# ContadorSincronico_SCH.net
KiCad netlist of a schematic drawn in Altium Designer
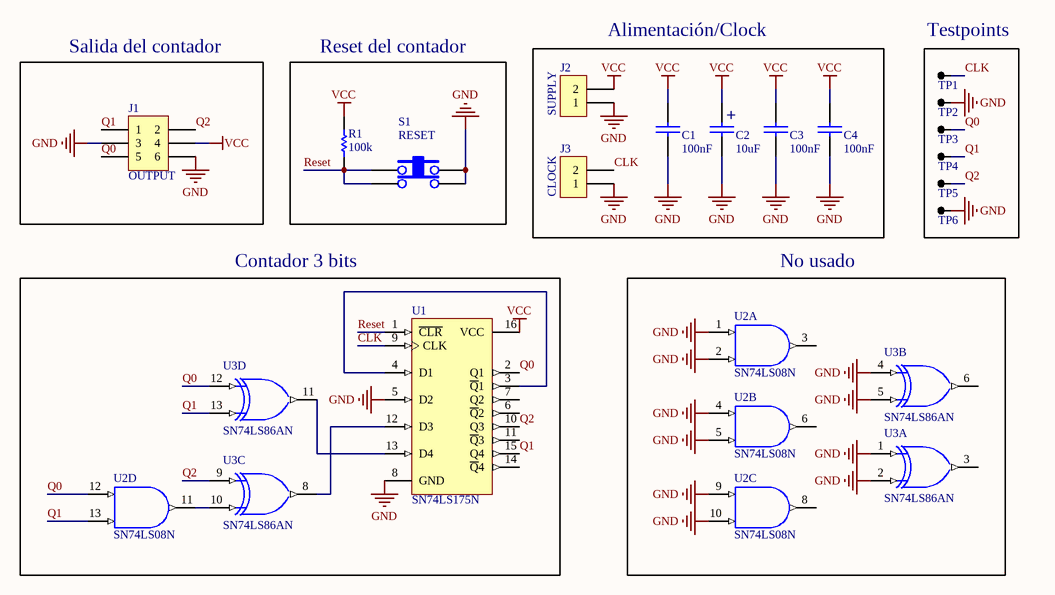
[diagram p0: ContadorSincronico_SCH.SchDoc]

(export (version "E")
  (design (tool "Eeschema 10.0.6"))
  (components
    (comp (ref "C1") (value "100nF") (footprint "0805") (libsource (lib "LIBEBAL") (part "CAP")))
    (comp (ref "C2") (value "10uF") (footprint "CAP100RP") (libsource (lib "LIBEBAL") (part "CAPPOL")))
    (comp (ref "C3") (value "100nF") (footprint "0805") (libsource (lib "LIBEBAL") (part "CAP")))
    (comp (ref "C4") (value "100nF") (footprint "0805") (libsource (lib "LIBEBAL") (part "CAP")))
    (comp (ref "J1") (value "OUTPUT") (footprint "SIP3*2") (libsource (lib "LIBEBAL") (part "CON3*2")))
    (comp (ref "J2") (value "SUPPLY") (footprint "BORNERA2") (libsource (lib "LIBEBAL") (part "BORNERA 2")))
    (comp (ref "J3") (value "CLOCK") (footprint "BORNERA2") (libsource (lib "LIBEBAL") (part "BORNERA 2")))
    (comp (ref "R1") (value "100k") (footprint "0805") (libsource (lib "LIBEBAL") (part "RES")))
    (comp (ref "S1")
      (value "RESET")
      (footprint "TACTSWITCH")
      (libsource (lib "LIBEBAL") (part "TACT SWITCH"))
    )
    (comp (ref "TP1") (value "CLK") (footprint "TPTH") (libsource (lib "LIBEBAL") (part "TP")))
    (comp (ref "TP2") (value "GND") (footprint "TPTH") (libsource (lib "LIBEBAL") (part "TP")))
    (comp (ref "TP3") (value "Q0") (footprint "TPTH") (libsource (lib "LIBEBAL") (part "TP")))
    (comp (ref "TP4") (value "Q1") (footprint "TPTH") (libsource (lib "LIBEBAL") (part "TP")))
    (comp (ref "TP5") (value "Q2") (footprint "TPTH") (libsource (lib "LIBEBAL") (part "TP")))
    (comp (ref "TP6") (value "GND") (footprint "TPTH") (libsource (lib "LIBEBAL") (part "TP")))
    (comp (ref "U1")
      (value "SN74LS175N")
      (footprint "N016")
      (description "Quadruple D-Type Flip-Flop with Clear")
      (fields (field (name "PUBLISHER") "Altium Limited"))
      (libsource (lib "TI Logic Flip-Flop") (part "SN74LS175N"))
    )
    (comp (ref "U2")
      (value "SN74LS08N")
      (footprint "N014")
      (description "Quadruple 2-Input Positive-AND Gate")
      (fields (field (name "PUBLISHER") "Altium Limited"))
      (libsource (lib "TI Logic Gate 2") (part "SN74LS08N"))
    )
    (comp (ref "U3")
      (value "SN74LS86AN")
      (footprint "N014")
      (description "Quadruple 2-Input Exclusive-OR Gate")
      (fields (field (name "PUBLISHER") "Altium Limited"))
      (libsource (lib "TI Logic Gate 2") (part "SN74LS86AN"))
    )
  )
  (nets
    (net (code "1") (name "/CLK") (class "Default")
      (node (ref "J3") (pin "2") (pinfunction "2_2") (pintype "passive"))
      (node (ref "TP1") (pin "1") (pinfunction "1_1") (pintype "passive"))
      (node (ref "U1") (pin "9") (pinfunction "CLK_9") (pintype "input"))
    )
    (net (code "2") (name "/Q0") (class "Default")
      (node (ref "J1") (pin "5") (pinfunction "5_5") (pintype "passive"))
      (node (ref "TP3") (pin "1") (pinfunction "1_1") (pintype "passive"))
      (node (ref "U1") (pin "2") (pinfunction "Q1_2") (pintype "output"))
      (node (ref "U2") (pin "12") (pinfunction "A_12") (pintype "input"))
      (node (ref "U3") (pin "12") (pinfunction "A_12") (pintype "input"))
    )
    (net (code "3") (name "/Q1") (class "Default")
      (node (ref "J1") (pin "1") (pinfunction "1_1") (pintype "passive"))
      (node (ref "TP4") (pin "1") (pinfunction "1_1") (pintype "passive"))
      (node (ref "U1") (pin "15") (pinfunction "Q4_15") (pintype "output"))
      (node (ref "U2") (pin "13") (pinfunction "B_13") (pintype "input"))
      (node (ref "U3") (pin "13") (pinfunction "B_13") (pintype "input"))
    )
    (net (code "4") (name "/Q2") (class "Default")
      (node (ref "J1") (pin "2") (pinfunction "2_2") (pintype "passive"))
      (node (ref "TP5") (pin "1") (pinfunction "1_1") (pintype "passive"))
      (node (ref "U1") (pin "10") (pinfunction "Q3_10") (pintype "output"))
      (node (ref "U3") (pin "9") (pinfunction "A_9") (pintype "input"))
    )
    (net (code "5") (name "/Reset") (class "Default")
      (node (ref "R1") (pin "2") (pinfunction "2_2") (pintype "passive"))
      (node (ref "S1") (pin "1") (pinfunction "1_1") (pintype "passive"))
      (node (ref "S1") (pin "2") (pinfunction "2_2") (pintype "passive"))
      (node (ref "U1") (pin "1") (pinfunction "~{CLR}_1") (pintype "input"))
    )
    (net (code "6") (name "GND") (class "Default")
      (node (ref "C1") (pin "2") (pinfunction "2_2") (pintype "passive"))
      (node (ref "C2") (pin "2") (pinfunction "2_2") (pintype "passive"))
      (node (ref "C3") (pin "2") (pinfunction "2_2") (pintype "passive"))
      (node (ref "C4") (pin "2") (pinfunction "2_2") (pintype "passive"))
      (node (ref "J1") (pin "3") (pinfunction "3_3") (pintype "passive"))
      (node (ref "J1") (pin "6") (pinfunction "6_6") (pintype "passive"))
      (node (ref "J2") (pin "1") (pinfunction "1_1") (pintype "passive"))
      (node (ref "J3") (pin "1") (pinfunction "1_1") (pintype "passive"))
      (node (ref "S1") (pin "3") (pinfunction "3_3") (pintype "passive"))
      (node (ref "S1") (pin "4") (pinfunction "4_4") (pintype "passive"))
      (node (ref "TP2") (pin "1") (pinfunction "1_1") (pintype "passive"))
      (node (ref "TP6") (pin "1") (pinfunction "1_1") (pintype "passive"))
      (node (ref "U1") (pin "5") (pinfunction "D2_5") (pintype "input"))
      (node (ref "U1") (pin "8") (pinfunction "GND_8") (pintype "power_in"))
      (node (ref "U2") (pin "1") (pinfunction "A_1") (pintype "input"))
      (node (ref "U2") (pin "10") (pinfunction "B_10") (pintype "input"))
      (node (ref "U2") (pin "2") (pinfunction "B_2") (pintype "input"))
      (node (ref "U2") (pin "4") (pinfunction "A_4") (pintype "input"))
      (node (ref "U2") (pin "5") (pinfunction "B_5") (pintype "input"))
      (node (ref "U2") (pin "7") (pinfunction "GND_7") (pintype "power_in"))
      (node (ref "U2") (pin "9") (pinfunction "A_9") (pintype "input"))
      (node (ref "U3") (pin "1") (pinfunction "A_1") (pintype "input"))
      (node (ref "U3") (pin "2") (pinfunction "B_2") (pintype "input"))
      (node (ref "U3") (pin "4") (pinfunction "A_4") (pintype "input"))
      (node (ref "U3") (pin "5") (pinfunction "B_5") (pintype "input"))
      (node (ref "U3") (pin "7") (pinfunction "GND_7") (pintype "power_in"))
    )
    (net (code "7") (name "Net-(U1-D1)") (class "Default")
      (node (ref "U1") (pin "3") (pinfunction "~{Q}1_3") (pintype "output"))
      (node (ref "U1") (pin "4") (pinfunction "D1_4") (pintype "input"))
    )
    (net (code "8") (name "Net-(U1-D3)") (class "Default")
      (node (ref "U1") (pin "12") (pinfunction "D3_12") (pintype "input"))
      (node (ref "U3") (pin "8") (pinfunction "Y_8") (pintype "output"))
    )
    (net (code "9") (name "Net-(U1-D4)") (class "Default")
      (node (ref "U1") (pin "13") (pinfunction "D4_13") (pintype "input"))
      (node (ref "U3") (pin "11") (pinfunction "Y_11") (pintype "output"))
    )
    (net (code "10") (name "Net-(U2D-Y)") (class "Default")
      (node (ref "U2") (pin "11") (pinfunction "Y_11") (pintype "output"))
      (node (ref "U3") (pin "10") (pinfunction "B_10") (pintype "input"))
    )
    (net (code "11") (name "VCC") (class "Default")
      (node (ref "C1") (pin "1") (pinfunction "1_1") (pintype "passive"))
      (node (ref "C2") (pin "1") (pinfunction "1_1") (pintype "passive"))
      (node (ref "C3") (pin "1") (pinfunction "1_1") (pintype "passive"))
      (node (ref "C4") (pin "1") (pinfunction "1_1") (pintype "passive"))
      (node (ref "J1") (pin "4") (pinfunction "4_4") (pintype "passive"))
      (node (ref "J2") (pin "2") (pinfunction "2_2") (pintype "passive"))
      (node (ref "R1") (pin "1") (pinfunction "1_1") (pintype "passive"))
      (node (ref "U1") (pin "16") (pinfunction "VCC_16") (pintype "power_in"))
      (node (ref "U2") (pin "14") (pinfunction "VCC_14") (pintype "power_in"))
      (node (ref "U3") (pin "14") (pinfunction "VCC_14") (pintype "power_in"))
    )
    (net (code "12") (name "unconnected-(U1-Q2-Pad7)") (class "Default")
      (node (ref "U1") (pin "7") (pinfunction "Q2_7") (pintype "output"))
    )
    (net (code "13") (name "unconnected-(U1-~{Q}2-Pad6)") (class "Default")
      (node (ref "U1") (pin "6") (pinfunction "~{Q}2_6") (pintype "output"))
    )
    (net (code "14") (name "unconnected-(U1-~{Q}3-Pad11)") (class "Default")
      (node (ref "U1") (pin "11") (pinfunction "~{Q}3_11") (pintype "output"))
    )
    (net (code "15") (name "unconnected-(U1-~{Q}4-Pad14)") (class "Default")
      (node (ref "U1") (pin "14") (pinfunction "~{Q}4_14") (pintype "output"))
    )
    (net (code "16") (name "unconnected-(U2A-Y-Pad3)") (class "Default")
      (node (ref "U2") (pin "3") (pinfunction "Y_3") (pintype "output"))
    )
    (net (code "17") (name "unconnected-(U2B-Y-Pad6)") (class "Default")
      (node (ref "U2") (pin "6") (pinfunction "Y_6") (pintype "output"))
    )
    (net (code "18") (name "unconnected-(U2C-Y-Pad8)") (class "Default")
      (node (ref "U2") (pin "8") (pinfunction "Y_8") (pintype "output"))
    )
    (net (code "19") (name "unconnected-(U3A-Y-Pad3)") (class "Default")
      (node (ref "U3") (pin "3") (pinfunction "Y_3") (pintype "output"))
    )
    (net (code "20") (name "unconnected-(U3B-Y-Pad6)") (class "Default")
      (node (ref "U3") (pin "6") (pinfunction "Y_6") (pintype "output"))
    )
  )
)
